# lora_esp32_gps.net
KiCad netlist of a schematic drawn in EAGLE
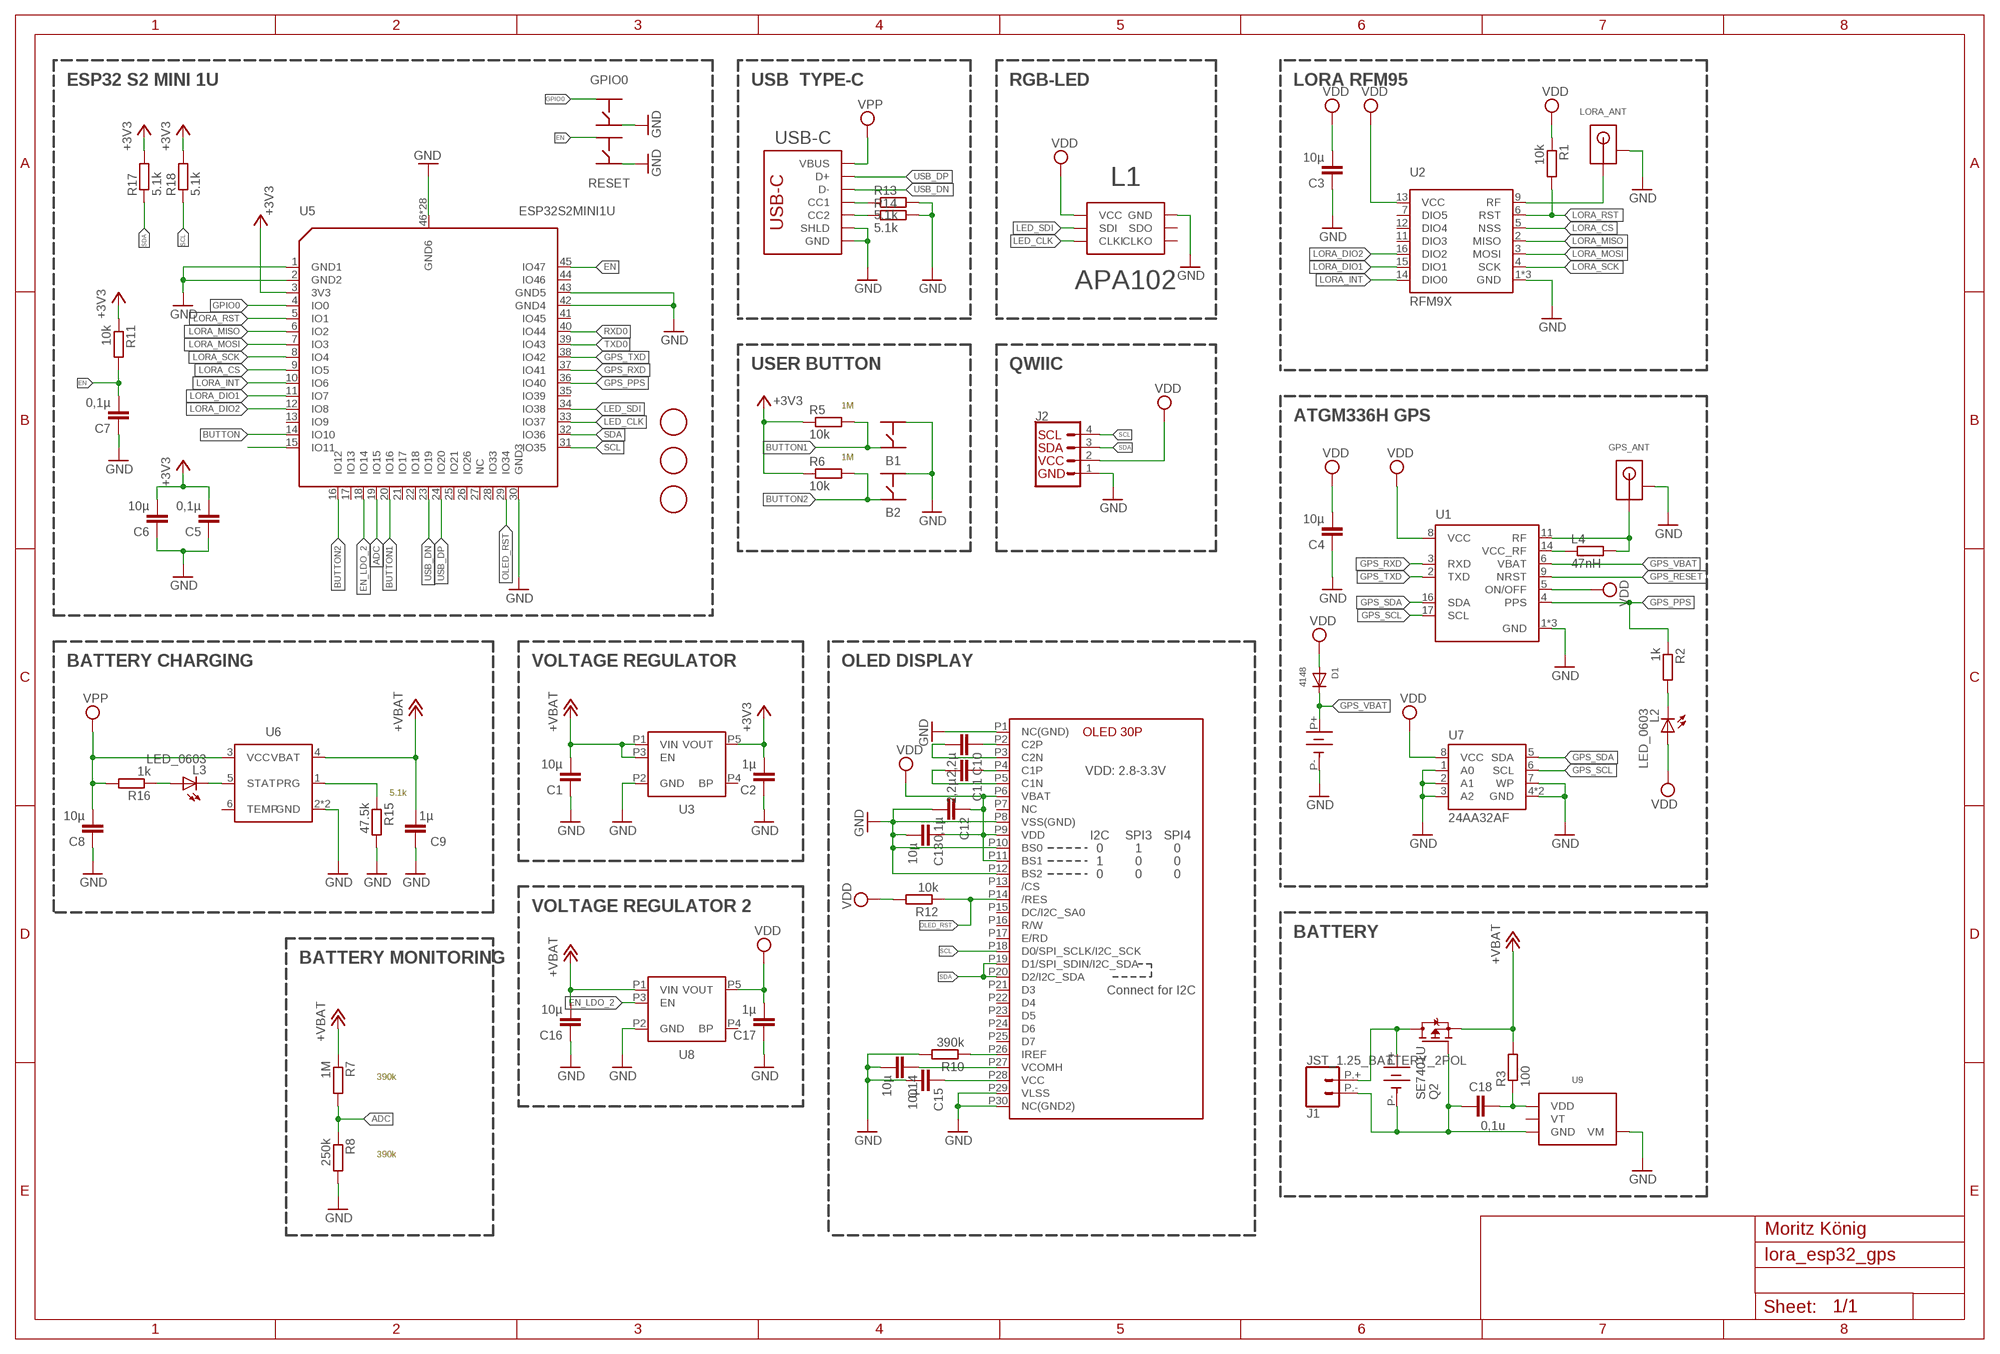
[diagram p0: schematic, sheet 1]

(export (version "E")
  (design (tool "Eeschema 10.0.6"))
  (components
    (comp (ref "B1")
      (value "PTS840ESDGMSMTRLFS")
      (footprint "eagle-import:PTS840ESDGMSMTRLFS")
      (libsource (lib "eagle-import") (part "PTS840ESDGMSMTRLFS"))
    )
    (comp (ref "B2")
      (value "PTS840ESDGMSMTRLFS")
      (footprint "eagle-import:PTS840ESDGMSMTRLFS")
      (libsource (lib "eagle-import") (part "PTS840ESDGMSMTRLFS"))
    )
    (comp (ref "BAT2")
      (value "MS621")
      (footprint "eagle-import:MS621")
      (libsource (lib "eagle-import") (part "MS621"))
    )
    (comp (ref "C1")
      (value "10µ")
      (footprint "eagle-import:C0603")
      (libsource (lib "eagle-import") (part "C-EU_WO_KEEPOUT"))
    )
    (comp (ref "C2")
      (value "1µ")
      (footprint "eagle-import:C0603")
      (libsource (lib "eagle-import") (part "C-EU_WO_KEEPOUT"))
    )
    (comp (ref "C3")
      (value "10µ")
      (footprint "eagle-import:C0603")
      (libsource (lib "eagle-import") (part "C0603"))
    )
    (comp (ref "C4")
      (value "10µ")
      (footprint "eagle-import:C0603")
      (libsource (lib "eagle-import") (part "C0603"))
    )
    (comp (ref "C5")
      (value "0,1µ")
      (footprint "eagle-import:C0603")
      (libsource (lib "eagle-import") (part "C-EU_WO_KEEPOUT"))
    )
    (comp (ref "C6")
      (value "10µ")
      (footprint "eagle-import:C0603")
      (libsource (lib "eagle-import") (part "C-EU_WO_KEEPOUT"))
    )
    (comp (ref "C7")
      (value "0,1µ")
      (footprint "eagle-import:C0603")
      (libsource (lib "eagle-import") (part "C0603"))
    )
    (comp (ref "C8")
      (value "10µ")
      (footprint "eagle-import:C0603")
      (libsource (lib "eagle-import") (part "C0603"))
    )
    (comp (ref "C9")
      (value "1µ")
      (footprint "eagle-import:C0603")
      (libsource (lib "eagle-import") (part "C0603"))
    )
    (comp (ref "C10")
      (value "2,2µ")
      (footprint "eagle-import:C0603")
      (libsource (lib "eagle-import") (part "C-EU_WO_KEEPOUT"))
    )
    (comp (ref "C11")
      (value "2,2µ")
      (footprint "eagle-import:C0603")
      (libsource (lib "eagle-import") (part "C-EU_WO_KEEPOUT"))
    )
    (comp (ref "C12")
      (value "0,1µ")
      (footprint "eagle-import:C0603")
      (libsource (lib "eagle-import") (part "C-EU_WO_KEEPOUT"))
    )
    (comp (ref "C13")
      (value "10µ")
      (footprint "eagle-import:C0603")
      (libsource (lib "eagle-import") (part "C-EU_WO_KEEPOUT"))
    )
    (comp (ref "C14")
      (value "10µ")
      (footprint "eagle-import:C0603")
      (libsource (lib "eagle-import") (part "C-EU_WO_KEEPOUT"))
    )
    (comp (ref "C15")
      (value "10µ")
      (footprint "eagle-import:C0603")
      (libsource (lib "eagle-import") (part "C-EU_WO_KEEPOUT"))
    )
    (comp (ref "C16")
      (value "10µ")
      (footprint "eagle-import:C0603")
      (libsource (lib "eagle-import") (part "C-EU_WO_KEEPOUT"))
    )
    (comp (ref "C17")
      (value "1µ")
      (footprint "eagle-import:C0603")
      (libsource (lib "eagle-import") (part "C-EU_WO_KEEPOUT"))
    )
    (comp (ref "C18")
      (value "0,1u")
      (footprint "eagle-import:C0603")
      (libsource (lib "eagle-import") (part "C0603"))
    )
    (comp (ref "D1")
      (value "4148")
      (footprint "eagle-import:SOD-323F")
      (libsource (lib "eagle-import") (part "DIODESOD-323F"))
    )
    (comp (ref "FID1")
      (value "FIDUCIAL")
      (footprint "eagle-import:FIDUCIAL_1MM")
      (libsource (lib "eagle-import") (part "FIDUCIAL"))
    )
    (comp (ref "FID2")
      (value "FIDUCIAL")
      (footprint "eagle-import:FIDUCIAL_1MM")
      (libsource (lib "eagle-import") (part "FIDUCIAL"))
    )
    (comp (ref "FID3")
      (value "FIDUCIAL")
      (footprint "eagle-import:FIDUCIAL_1MM")
      (libsource (lib "eagle-import") (part "FIDUCIAL"))
    )
    (comp (ref "GPIO0")
      (value "BUTTON_4PIN_TS_1177")
      (footprint "eagle-import:TS-1177-C-B-B")
      (libsource (lib "eagle-import") (part "BUTTON_4PIN_TS_1177"))
    )
    (comp (ref "GPS_ANT")
      (value "UFL_ANT_CONNECTOR")
      (footprint "eagle-import:UFL_ANT_CONNECTOR")
      (libsource (lib "eagle-import") (part "UFL_ANT_CONNECTOR"))
    )
    (comp (ref "J1")
      (value "JST_1.25_BATTERY_2POL")
      (footprint "eagle-import:JST_1.25MM_2POL")
      (libsource (lib "eagle-import") (part "JST_1.25_BATTERY_2POL"))
    )
    (comp (ref "J2")
      (value "QWIIC_CONNECTORJS-1MM")
      (footprint "eagle-import:1X04_1MM_RA")
      (libsource (lib "eagle-import") (part "QWIIC_CONNECTORJS-1MM"))
    )
    (comp (ref "L1")
      (value "APA102_2020")
      (footprint "eagle-import:APA102_2020")
      (libsource (lib "eagle-import") (part "APA102_2020"))
    )
    (comp (ref "L2")
      (value "LED_0603")
      (footprint "eagle-import:CHIPLED_0603")
      (libsource (lib "eagle-import") (part "LED_0603"))
    )
    (comp (ref "L3")
      (value "LED_0603")
      (footprint "eagle-import:CHIPLED_0603")
      (libsource (lib "eagle-import") (part "LED_0603"))
    )
    (comp (ref "L4")
      (value "47nH")
      (footprint "eagle-import:R0402")
      (libsource (lib "eagle-import") (part "R0402"))
    )
    (comp (ref "LORA_ANT")
      (value "UFL_ANT_CONNECTOR")
      (footprint "eagle-import:UFL_ANT_CONNECTOR")
      (libsource (lib "eagle-import") (part "UFL_ANT_CONNECTOR"))
    )
    (comp (ref "Q2")
      (value "SE7401U")
      (footprint "eagle-import:SOT323")
      (libsource (lib "eagle-import") (part "SE7401U"))
    )
    (comp (ref "R1")
      (value "10k")
      (footprint "eagle-import:R0603")
      (libsource (lib "eagle-import") (part "R0603"))
    )
    (comp (ref "R2")
      (value "1k")
      (footprint "eagle-import:R0603")
      (libsource (lib "eagle-import") (part "R0603"))
    )
    (comp (ref "R3")
      (value "100")
      (footprint "eagle-import:R0603")
      (libsource (lib "eagle-import") (part "R0603"))
    )
    (comp (ref "R5")
      (value "10k")
      (footprint "eagle-import:R0603")
      (libsource (lib "eagle-import") (part "R0603"))
    )
    (comp (ref "R6")
      (value "10k")
      (footprint "eagle-import:R0603")
      (libsource (lib "eagle-import") (part "R0603"))
    )
    (comp (ref "R7")
      (value "1M")
      (footprint "eagle-import:R0603")
      (libsource (lib "eagle-import") (part "R0603"))
    )
    (comp (ref "R8")
      (value "250k")
      (footprint "eagle-import:R0603")
      (libsource (lib "eagle-import") (part "R0603"))
    )
    (comp (ref "R10")
      (value "390k")
      (footprint "eagle-import:R0603")
      (libsource (lib "eagle-import") (part "R-EU_WO_KEEPOUT"))
    )
    (comp (ref "R11")
      (value "10k")
      (footprint "eagle-import:R0603")
      (libsource (lib "eagle-import") (part "R0603"))
    )
    (comp (ref "R12")
      (value "10k")
      (footprint "eagle-import:R0603")
      (libsource (lib "eagle-import") (part "R-EU_WO_KEEPOUT"))
    )
    (comp (ref "R13")
      (value "5.1k")
      (footprint "eagle-import:R0603")
      (libsource (lib "eagle-import") (part "R0603"))
    )
    (comp (ref "R14")
      (value "5.1k")
      (footprint "eagle-import:R0603")
      (libsource (lib "eagle-import") (part "R0603"))
    )
    (comp (ref "R15")
      (value "47.5k")
      (footprint "eagle-import:R0603")
      (libsource (lib "eagle-import") (part "R0603"))
    )
    (comp (ref "R16")
      (value "1k")
      (footprint "eagle-import:R0603")
      (libsource (lib "eagle-import") (part "R0603"))
    )
    (comp (ref "R17")
      (value "5.1k")
      (footprint "eagle-import:R0603")
      (libsource (lib "eagle-import") (part "R-EU_WO_KEEPOUT"))
    )
    (comp (ref "R18")
      (value "5.1k")
      (footprint "eagle-import:R0603")
      (libsource (lib "eagle-import") (part "R-EU_WO_KEEPOUT"))
    )
    (comp (ref "RESET")
      (value "BUTTON_4PIN_TS_1177")
      (footprint "eagle-import:TS-1177-C-B-B")
      (libsource (lib "eagle-import") (part "BUTTON_4PIN_TS_1177"))
    )
    (comp (ref "U$2")
      (value "BATTERY_KEYSTONE_1051")
      (footprint "eagle-import:KEYSTONE_1051")
      (libsource (lib "eagle-import") (part "BATTERY_KEYSTONE_1051"))
    )
    (comp (ref "U1")
      (value "ATGM336H")
      (footprint "eagle-import:ATGM336H-MODULE")
      (libsource (lib "eagle-import") (part "ATGM336H"))
    )
    (comp (ref "U2")
      (value "RFM9X")
      (footprint "eagle-import:LORA_RFM9X")
      (libsource (lib "eagle-import") (part "RFM9X"))
    )
    (comp (ref "U3")
      (value "RT9193_SC70-5")
      (footprint "eagle-import:SC-70-5")
      (libsource (lib "eagle-import") (part "RT9193_SC70-5"))
    )
    (comp (ref "U4")
      (value "OLD_096_SSD1306_30P_2B")
      (footprint "eagle-import:OLED_096_30P_B")
      (libsource (lib "eagle-import") (part "OLD_096_SSD1306_30P_2B"))
    )
    (comp (ref "U5")
      (value "ESP32S2MINI1U")
      (footprint "eagle-import:ESP32-S2-MINI-1U")
      (libsource (lib "eagle-import") (part "ESP32-S2-MINI-1U"))
    )
    (comp (ref "U6")
      (value "WS4518D")
      (footprint "eagle-import:DFN-6")
      (libsource (lib "eagle-import") (part "WS4518D"))
    )
    (comp (ref "U7")
      (value "24AA32AF")
      (footprint "eagle-import:TDFN8")
      (libsource (lib "eagle-import") (part "24AA32AF"))
    )
    (comp (ref "U8")
      (value "RT9193_SC70-5")
      (footprint "eagle-import:SC-70-5")
      (libsource (lib "eagle-import") (part "RT9193_SC70-5"))
    )
    (comp (ref "U9")
      (value "XB5353A")
      (footprint "eagle-import:SOT23-5")
      (libsource (lib "eagle-import") (part "XB5353A"))
    )
    (comp (ref "USB-C")
      (value "USB_C_C393939")
      (footprint "eagle-import:USBC_C393939")
      (libsource (lib "eagle-import") (part "USB_C_C393939"))
    )
  )
  (nets
    (net (code "1") (name "+3V3") (class "Default")
      (node (ref "C2") (pin "2") (pinfunction "2_2") (pintype "passive"))
      (node (ref "C5") (pin "2") (pinfunction "2_2") (pintype "passive"))
      (node (ref "C6") (pin "2") (pinfunction "2_2") (pintype "passive"))
      (node (ref "R11") (pin "1") (pinfunction "1_1") (pintype "passive"))
      (node (ref "R17") (pin "2") (pinfunction "2_2") (pintype "passive"))
      (node (ref "R18") (pin "2") (pinfunction "2_2") (pintype "passive"))
      (node (ref "R5") (pin "1") (pinfunction "1_1") (pintype "passive"))
      (node (ref "R6") (pin "1") (pinfunction "1_1") (pintype "passive"))
      (node (ref "U3") (pin "P5") (pinfunction "VOUT_P5") (pintype "bidirectional"))
      (node (ref "U5") (pin "3") (pinfunction "3V3_3") (pintype "bidirectional"))
    )
    (net (code "2") (name "+VBAT") (class "Default")
      (node (ref "C1") (pin "2") (pinfunction "2_2") (pintype "passive"))
      (node (ref "C16") (pin "2") (pinfunction "2_2") (pintype "passive"))
      (node (ref "C9") (pin "2") (pinfunction "2_2") (pintype "passive"))
      (node (ref "Q2") (pin "2") (pinfunction "S_2") (pintype "passive"))
      (node (ref "R3") (pin "2") (pinfunction "2_2") (pintype "passive"))
      (node (ref "R7") (pin "1") (pinfunction "1_1") (pintype "passive"))
      (node (ref "U3") (pin "P1") (pinfunction "VIN_P1") (pintype "bidirectional"))
      (node (ref "U3") (pin "P3") (pinfunction "EN_P3") (pintype "bidirectional"))
      (node (ref "U6") (pin "4") (pinfunction "VBAT_4") (pintype "bidirectional"))
      (node (ref "U8") (pin "P1") (pinfunction "VIN_P1") (pintype "bidirectional"))
    )
    (net (code "3") (name "ADC") (class "Default")
      (node (ref "R7") (pin "2") (pinfunction "2_2") (pintype "passive"))
      (node (ref "R8") (pin "1") (pinfunction "1_1") (pintype "passive"))
      (node (ref "U5") (pin "19") (pinfunction "IO15_19") (pintype "bidirectional"))
    )
    (net (code "4") (name "BUTTON") (class "Default")
      (node (ref "U5") (pin "14") (pinfunction "IO10_14") (pintype "bidirectional"))
    )
    (net (code "5") (name "BUTTON1") (class "Default")
      (node (ref "B1") (pin "2") (pinfunction "2_2") (pintype "bidirectional"))
      (node (ref "R5") (pin "2") (pinfunction "2_2") (pintype "passive"))
      (node (ref "U5") (pin "20") (pinfunction "IO16_20") (pintype "bidirectional"))
    )
    (net (code "6") (name "BUTTON2") (class "Default")
      (node (ref "B2") (pin "2") (pinfunction "2_2") (pintype "bidirectional"))
      (node (ref "R6") (pin "2") (pinfunction "2_2") (pintype "passive"))
      (node (ref "U5") (pin "16") (pinfunction "IO12_16") (pintype "bidirectional"))
    )
    (net (code "7") (name "EN") (class "Default")
      (node (ref "C7") (pin "2") (pinfunction "2_2") (pintype "passive"))
      (node (ref "R11") (pin "2") (pinfunction "2_2") (pintype "passive"))
      (node (ref "RESET") (pin "P4") (pinfunction "4_P4") (pintype "bidirectional"))
      (node (ref "U5") (pin "45") (pinfunction "IO47_45") (pintype "bidirectional"))
    )
    (net (code "8") (name "EN_LDO_2") (class "Default")
      (node (ref "U5") (pin "18") (pinfunction "IO14_18") (pintype "bidirectional"))
      (node (ref "U8") (pin "P3") (pinfunction "EN_P3") (pintype "bidirectional"))
    )
    (net (code "9") (name "GND") (class "Default")
      (node (ref "B1") (pin "3") (pinfunction "3_3") (pintype "bidirectional"))
      (node (ref "B2") (pin "3") (pinfunction "3_3") (pintype "bidirectional"))
      (node (ref "BAT2") (pin "P-") (pinfunction "GND_P-") (pintype "bidirectional"))
      (node (ref "C1") (pin "1") (pinfunction "1_1") (pintype "passive"))
      (node (ref "C12") (pin "2") (pinfunction "2_2") (pintype "passive"))
      (node (ref "C13") (pin "2") (pinfunction "2_2") (pintype "passive"))
      (node (ref "C14") (pin "2") (pinfunction "2_2") (pintype "passive"))
      (node (ref "C15") (pin "2") (pinfunction "2_2") (pintype "passive"))
      (node (ref "C16") (pin "1") (pinfunction "1_1") (pintype "passive"))
      (node (ref "C17") (pin "1") (pinfunction "1_1") (pintype "passive"))
      (node (ref "C2") (pin "1") (pinfunction "1_1") (pintype "passive"))
      (node (ref "C3") (pin "1") (pinfunction "1_1") (pintype "passive"))
      (node (ref "C4") (pin "1") (pinfunction "1_1") (pintype "passive"))
      (node (ref "C5") (pin "1") (pinfunction "1_1") (pintype "passive"))
      (node (ref "C6") (pin "1") (pinfunction "1_1") (pintype "passive"))
      (node (ref "C7") (pin "1") (pinfunction "1_1") (pintype "passive"))
      (node (ref "C8") (pin "1") (pinfunction "1_1") (pintype "passive"))
      (node (ref "C9") (pin "1") (pinfunction "1_1") (pintype "passive"))
      (node (ref "GPIO0") (pin "P1") (pinfunction "1_P1") (pintype "bidirectional"))
      (node (ref "GPS_ANT") (pin "P1.-") (pinfunction "GND_P1.-") (pintype "bidirectional"))
      (node (ref "GPS_ANT") (pin "P2.-") (pinfunction "GND_P2.-") (pintype "bidirectional"))
      (node (ref "J2") (pin "1") (pinfunction "GND_1") (pintype "power_in"))
      (node (ref "L1") (pin "P6") (pinfunction "GND_P6") (pintype "bidirectional"))
      (node (ref "L1") (pin "P6.1") (pinfunction "GND_P6.1") (pintype "bidirectional"))
      (node (ref "LORA_ANT") (pin "P1.-") (pinfunction "GND_P1.-") (pintype "bidirectional"))
      (node (ref "LORA_ANT") (pin "P2.-") (pinfunction "GND_P2.-") (pintype "bidirectional"))
      (node (ref "R10") (pin "2") (pinfunction "2_2") (pintype "passive"))
      (node (ref "R13") (pin "2") (pinfunction "2_2") (pintype "passive"))
      (node (ref "R14") (pin "2") (pinfunction "2_2") (pintype "passive"))
      (node (ref "R15") (pin "2") (pinfunction "2_2") (pintype "passive"))
      (node (ref "R8") (pin "2") (pinfunction "2_2") (pintype "passive"))
      (node (ref "RESET") (pin "P1") (pinfunction "1_P1") (pintype "bidirectional"))
      (node (ref "U1") (pin "1") (pinfunction "GND_1") (pintype "bidirectional"))
      (node (ref "U1") (pin "10") (pinfunction "GND_10") (pintype "bidirectional"))
      (node (ref "U1") (pin "12") (pinfunction "GND_12") (pintype "bidirectional"))
      (node (ref "U2") (pin "1") (pinfunction "GND_1") (pintype "bidirectional"))
      (node (ref "U2") (pin "10") (pinfunction "GND_10") (pintype "bidirectional"))
      (node (ref "U2") (pin "8") (pinfunction "GND_8") (pintype "bidirectional"))
      (node (ref "U3") (pin "P2") (pinfunction "GND_P2") (pintype "bidirectional"))
      (node (ref "U4") (pin "P1") (pinfunction "NC(GND)_P1") (pintype "bidirectional"))
      (node (ref "U4") (pin "P10") (pinfunction "BS0_P10") (pintype "bidirectional"))
      (node (ref "U4") (pin "P12") (pinfunction "BS2_P12") (pintype "bidirectional"))
      (node (ref "U4") (pin "P29") (pinfunction "VLSS_P29") (pintype "bidirectional"))
      (node (ref "U4") (pin "P30") (pinfunction "NC(GND2)_P30") (pintype "bidirectional"))
      (node (ref "U4") (pin "P8") (pinfunction "VSS(GND)_P8") (pintype "bidirectional"))
      (node (ref "U5") (pin "1") (pinfunction "GND1_1") (pintype "bidirectional"))
      (node (ref "U5") (pin "2") (pinfunction "GND2_2") (pintype "bidirectional"))
      (node (ref "U5") (pin "30") (pinfunction "GND3_30") (pintype "bidirectional"))
      (node (ref "U5") (pin "42") (pinfunction "GND4_42") (pintype "bidirectional"))
      (node (ref "U5") (pin "43") (pinfunction "GND5_43") (pintype "bidirectional"))
      (node (ref "U5") (pin "46") (pinfunction "GND6_46") (pintype "bidirectional"))
      (node (ref "U5") (pin "47") (pinfunction "GND6_47") (pintype "bidirectional"))
      (node (ref "U5") (pin "48") (pinfunction "GND6_48") (pintype "bidirectional"))
      (node (ref "U5") (pin "49") (pinfunction "GND6_49") (pintype "bidirectional"))
      (node (ref "U5") (pin "50") (pinfunction "GND6_50") (pintype "bidirectional"))
      (node (ref "U5") (pin "51") (pinfunction "GND6_51") (pintype "bidirectional"))
      (node (ref "U5") (pin "52") (pinfunction "GND6_52") (pintype "bidirectional"))
      (node (ref "U5") (pin "53") (pinfunction "GND6_53") (pintype "bidirectional"))
      (node (ref "U5") (pin "54") (pinfunction "GND6_54") (pintype "bidirectional"))
      (node (ref "U5") (pin "55") (pinfunction "GND6_55") (pintype "bidirectional"))
      (node (ref "U5") (pin "56") (pinfunction "GND6_56") (pintype "bidirectional"))
      (node (ref "U5") (pin "57") (pinfunction "GND6_57") (pintype "bidirectional"))
      (node (ref "U5") (pin "58") (pinfunction "GND6_58") (pintype "bidirectional"))
      (node (ref "U5") (pin "59") (pinfunction "GND6_59") (pintype "bidirectional"))
      (node (ref "U5") (pin "60") (pinfunction "GND6_60") (pintype "bidirectional"))
      (node (ref "U5") (pin "61") (pinfunction "GND6_61") (pintype "bidirectional"))
      (node (ref "U5") (pin "62") (pinfunction "GND6_62") (pintype "bidirectional"))
      (node (ref "U5") (pin "63") (pinfunction "GND6_63") (pintype "bidirectional"))
      (node (ref "U5") (pin "64") (pinfunction "GND6_64") (pintype "bidirectional"))
      (node (ref "U5") (pin "65") (pinfunction "GND6_65") (pintype "bidirectional"))
      (node (ref "U5") (pin "66") (pinfunction "GND6_66") (pintype "bidirectional"))
      (node (ref "U5") (pin "67") (pinfunction "GND6_67") (pintype "bidirectional"))
      (node (ref "U5") (pin "68") (pinfunction "GND6_68") (pintype "bidirectional"))
      (node (ref "U5") (pin "69") (pinfunction "GND6_69") (pintype "bidirectional"))
      (node (ref "U5") (pin "70") (pinfunction "GND6_70") (pintype "bidirectional"))
      (node (ref "U5") (pin "71") (pinfunction "GND6_71") (pintype "bidirectional"))
      (node (ref "U5") (pin "72") (pinfunction "GND6_72") (pintype "bidirectional"))
      (node (ref "U5") (pin "73") (pinfunction "GND6_73") (pintype "bidirectional"))
      (node (ref "U6") (pin "2") (pinfunction "GND_2") (pintype "bidirectional"))
      (node (ref "U6") (pin "EXP") (pinfunction "GND_EXP") (pintype "bidirectional"))
      (node (ref "U7") (pin "1") (pinfunction "A0_1") (pintype "bidirectional"))
      (node (ref "U7") (pin "2") (pinfunction "A1_2") (pintype "bidirectional"))
      (node (ref "U7") (pin "3") (pinfunction "A2_3") (pintype "bidirectional"))
      (node (ref "U7") (pin "4") (pinfunction "GND_4") (pintype "bidirectional"))
      (node (ref "U7") (pin "7") (pinfunction "WP_7") (pintype "bidirectional"))
      (node (ref "U7") (pin "EXP") (pinfunction "GND_EXP") (pintype "bidirectional"))
      (node (ref "U8") (pin "P2") (pinfunction "GND_P2") (pintype "bidirectional"))
      (node (ref "U9") (pin "4") (pinfunction "VM_4") (pintype "bidirectional"))
      (node (ref "U9") (pin "5") (pinfunction "VM_5") (pintype "bidirectional"))
      (node (ref "USB-C") (pin "A1B12") (pinfunction "GND_A1B12") (pintype "bidirectional"))
      (node (ref "USB-C") (pin "B1A12") (pinfunction "GND_B1A12") (pintype "bidirectional"))
      (node (ref "USB-C") (pin "S1") (pinfunction "SHLD_S1") (pintype "bidirectional"))
      (node (ref "USB-C") (pin "S2") (pinfunction "SHLD_S2") (pintype "bidirectional"))
      (node (ref "USB-C") (pin "S3") (pinfunction "SHLD_S3") (pintype "bidirectional"))
      (node (ref "USB-C") (pin "S4") (pinfunction "SHLD_S4") (pintype "bidirectional"))
    )
    (net (code "10") (name "GPIO0") (class "Default")
      (node (ref "GPIO0") (pin "P4") (pinfunction "4_P4") (pintype "bidirectional"))
      (node (ref "U5") (pin "4") (pinfunction "IO0_4") (pintype "bidirectional"))
    )
    (net (code "11") (name "GPS_PPS") (class "Default")
      (node (ref "R2") (pin "1") (pinfunction "1_1") (pintype "passive"))
      (node (ref "U1") (pin "4") (pinfunction "PPS_4") (pintype "bidirectional"))
      (node (ref "U5") (pin "36") (pinfunction "IO40_36") (pintype "bidirectional"))
    )
    (net (code "12") (name "GPS_RESET") (class "Default")
      (node (ref "U1") (pin "9") (pinfunction "NRST_9") (pintype "bidirectional"))
    )
    (net (code "13") (name "GPS_RXD") (class "Default")
      (node (ref "U1") (pin "3") (pinfunction "RXD_3") (pintype "bidirectional"))
      (node (ref "U5") (pin "37") (pinfunction "IO41_37") (pintype "bidirectional"))
    )
    (net (code "14") (name "GPS_SCL") (class "Default")
      (node (ref "U1") (pin "17") (pinfunction "SCL_17") (pintype "bidirectional"))
      (node (ref "U7") (pin "6") (pinfunction "SCL_6") (pintype "bidirectional"))
    )
    (net (code "15") (name "GPS_SDA") (class "Default")
      (node (ref "U1") (pin "16") (pinfunction "SDA_16") (pintype "bidirectional"))
      (node (ref "U7") (pin "5") (pinfunction "SDA_5") (pintype "bidirectional"))
    )
    (net (code "16") (name "GPS_TXD") (class "Default")
      (node (ref "U1") (pin "2") (pinfunction "TXD_2") (pintype "bidirectional"))
      (node (ref "U5") (pin "38") (pinfunction "IO42_38") (pintype "bidirectional"))
    )
    (net (code "17") (name "GPS_VBAT") (class "Default")
      (node (ref "BAT2") (pin "P+") (pinfunction "VCC_P+") (pintype "bidirectional"))
      (node (ref "D1") (pin "C") (pinfunction "C_C") (pintype "passive"))
      (node (ref "U1") (pin "6") (pinfunction "VBAT_6") (pintype "bidirectional"))
    )
    (net (code "18") (name "LED_CLK") (class "Default")
      (node (ref "L1") (pin "P5") (pinfunction "CLKI_P5") (pintype "bidirectional"))
      (node (ref "U5") (pin "33") (pinfunction "IO37_33") (pintype "bidirectional"))
    )
    (net (code "19") (name "LED_SDI") (class "Default")
      (node (ref "L1") (pin "P4") (pinfunction "SDI_P4") (pintype "bidirectional"))
      (node (ref "U5") (pin "34") (pinfunction "IO38_34") (pintype "bidirectional"))
    )
    (net (code "20") (name "LORA_CS") (class "Default")
      (node (ref "U2") (pin "5") (pinfunction "NSS_5") (pintype "bidirectional"))
      (node (ref "U5") (pin "9") (pinfunction "IO5_9") (pintype "bidirectional"))
    )
    (net (code "21") (name "LORA_DIO1") (class "Default")
      (node (ref "U2") (pin "15") (pinfunction "DIO1_15") (pintype "bidirectional"))
      (node (ref "U5") (pin "11") (pinfunction "IO7_11") (pintype "bidirectional"))
    )
    (net (code "22") (name "LORA_DIO2") (class "Default")
      (node (ref "U2") (pin "16") (pinfunction "DIO2_16") (pintype "bidirectional"))
      (node (ref "U5") (pin "12") (pinfunction "IO8_12") (pintype "bidirectional"))
    )
    (net (code "23") (name "LORA_INT") (class "Default")
      (node (ref "U2") (pin "14") (pinfunction "DIO0_14") (pintype "bidirectional"))
      (node (ref "U5") (pin "10") (pinfunction "IO6_10") (pintype "bidirectional"))
    )
    (net (code "24") (name "LORA_MISO") (class "Default")
      (node (ref "U2") (pin "2") (pinfunction "MISO_2") (pintype "bidirectional"))
      (node (ref "U5") (pin "6") (pinfunction "IO2_6") (pintype "bidirectional"))
    )
    (net (code "25") (name "LORA_MOSI") (class "Default")
      (node (ref "U2") (pin "3") (pinfunction "MOSI_3") (pintype "bidirectional"))
      (node (ref "U5") (pin "7") (pinfunction "IO3_7") (pintype "bidirectional"))
    )
    (net (code "26") (name "LORA_RST") (class "Default")
      (node (ref "R1") (pin "2") (pinfunction "2_2") (pintype "passive"))
      (node (ref "U2") (pin "6") (pinfunction "RST_6") (pintype "bidirectional"))
      (node (ref "U5") (pin "5") (pinfunction "IO1_5") (pintype "bidirectional"))
    )
    (net (code "27") (name "LORA_SCK") (class "Default")
      (node (ref "U2") (pin "4") (pinfunction "SCK_4") (pintype "bidirectional"))
      (node (ref "U5") (pin "8") (pinfunction "IO4_8") (pintype "bidirectional"))
    )
    (net (code "28") (name "Net-(J1-1)") (class "Default")
      (node (ref "J1") (pin "P.+") (pinfunction "1_P.+") (pintype "passive"))
      (node (ref "Q2") (pin "3") (pinfunction "D_3") (pintype "passive"))
      (node (ref "U$2") (pin "P+") (pinfunction "VCC_P+") (pintype "bidirectional"))
    )
    (net (code "29") (name "Net-(J1-2)") (class "Default")
      (node (ref "C18") (pin "1") (pinfunction "1_1") (pintype "passive"))
      (node (ref "J1") (pin "P.-") (pinfunction "2_P.-") (pintype "passive"))
      (node (ref "Q2") (pin "1") (pinfunction "G_1") (pintype "passive"))
      (node (ref "U$2") (pin "P-") (pinfunction "GND_P-") (pintype "bidirectional"))
      (node (ref "U9") (pin "2") (pinfunction "GND_2") (pintype "bidirectional"))
    )
    (net (code "30") (name "Net-(L2-C)") (class "Default")
      (node (ref "L2") (pin "P$1") (pinfunction "C_P$1") (pintype "passive"))
      (node (ref "R2") (pin "2") (pinfunction "2_2") (pintype "passive"))
    )
    (net (code "31") (name "Net-(L3-A)") (class "Default")
      (node (ref "L3") (pin "P$2") (pinfunction "A_P$2") (pintype "passive"))
      (node (ref "R16") (pin "1") (pinfunction "1_1") (pintype "passive"))
    )
    (net (code "32") (name "Net-(L3-C)") (class "Default")
      (node (ref "L3") (pin "P$1") (pinfunction "C_P$1") (pintype "passive"))
      (node (ref "U6") (pin "5") (pinfunction "STAT_5") (pintype "bidirectional"))
    )
    (net (code "33") (name "Net-(U1-RF)") (class "Default")
      (node (ref "GPS_ANT") (pin "ANT") (pinfunction "ANT_ANT") (pintype "bidirectional"))
      (node (ref "L4") (pin "2") (pinfunction "2_2") (pintype "passive"))
      (node (ref "U1") (pin "11") (pinfunction "RF_11") (pintype "bidirectional"))
    )
    (net (code "34") (name "Net-(U1-VCC_RF)") (class "Default")
      (node (ref "L4") (pin "1") (pinfunction "1_1") (pintype "passive"))
      (node (ref "U1") (pin "14") (pinfunction "VCC_RF_14") (pintype "bidirectional"))
    )
    (net (code "35") (name "Net-(U2-RF)") (class "Default")
      (node (ref "LORA_ANT") (pin "ANT") (pinfunction "ANT_ANT") (pintype "bidirectional"))
      (node (ref "U2") (pin "9") (pinfunction "RF_9") (pintype "bidirectional"))
    )
    (net (code "36") (name "Net-(U4-C1N)") (class "Default")
      (node (ref "C11") (pin "2") (pinfunction "2_2") (pintype "passive"))
      (node (ref "U4") (pin "P5") (pinfunction "C1N_P5") (pintype "bidirectional"))
    )
    (net (code "37") (name "Net-(U4-C1P)") (class "Default")
      (node (ref "C11") (pin "1") (pinfunction "1_1") (pintype "passive"))
      (node (ref "U4") (pin "P4") (pinfunction "C1P_P4") (pintype "bidirectional"))
    )
    (net (code "38") (name "Net-(U4-C2N)") (class "Default")
      (node (ref "C10") (pin "2") (pinfunction "2_2") (pintype "passive"))
      (node (ref "U4") (pin "P3") (pinfunction "C2N_P3") (pintype "bidirectional"))
    )
    (net (code "39") (name "Net-(U4-C2P)") (class "Default")
      (node (ref "C10") (pin "1") (pinfunction "1_1") (pintype "passive"))
      (node (ref "U4") (pin "P2") (pinfunction "C2P_P2") (pintype "bidirectional"))
    )
    (net (code "40") (name "Net-(U4-IREF)") (class "Default")
      (node (ref "R10") (pin "1") (pinfunction "1_1") (pintype "passive"))
      (node (ref "U4") (pin "P26") (pinfunction "IREF_P26") (pintype "bidirectional"))
    )
    (net (code "41") (name "Net-(U4-VCC)") (class "Default")
      (node (ref "C15") (pin "1") (pinfunction "1_1") (pintype "passive"))
      (node (ref "U4") (pin "P28") (pinfunction "VCC_P28") (pintype "bidirectional"))
    )
    (net (code "42") (name "Net-(U4-VCOMH)") (class "Default")
      (node (ref "C14") (pin "1") (pinfunction "1_1") (pintype "passive"))
      (node (ref "U4") (pin "P27") (pinfunction "VCOMH_P27") (pintype "bidirectional"))
    )
    (net (code "43") (name "Net-(U6-PRG)") (class "Default")
      (node (ref "R15") (pin "1") (pinfunction "1_1") (pintype "passive"))
      (node (ref "U6") (pin "1") (pinfunction "PRG_1") (pintype "bidirectional"))
    )
    (net (code "44") (name "Net-(U9-VDD)") (class "Default")
      (node (ref "C18") (pin "2") (pinfunction "2_2") (pintype "passive"))
      (node (ref "R3") (pin "1") (pinfunction "1_1") (pintype "passive"))
      (node (ref "U9") (pin "3") (pinfunction "VDD_3") (pintype "bidirectional"))
    )
    (net (code "45") (name "Net-(USB-C-CC1)") (class "Default")
      (node (ref "R13") (pin "1") (pinfunction "1_1") (pintype "passive"))
      (node (ref "USB-C") (pin "A5") (pinfunction "CC1_A5") (pintype "bidirectional"))
    )
    (net (code "46") (name "Net-(USB-C-CC2)") (class "Default")
      (node (ref "R14") (pin "1") (pinfunction "1_1") (pintype "passive"))
      (node (ref "USB-C") (pin "B5") (pinfunction "CC2_B5") (pintype "bidirectional"))
    )
    (net (code "47") (name "OLED_RST") (class "Default")
      (node (ref "R12") (pin "1") (pinfunction "1_1") (pintype "passive"))
      (node (ref "U4") (pin "P14") (pinfunction "/RES_P14") (pintype "bidirectional"))
      (node (ref "U5") (pin "29") (pinfunction "IO34_29") (pintype "bidirectional"))
    )
    (net (code "48") (name "RXD0") (class "Default")
      (node (ref "U5") (pin "40") (pinfunction "IO44_40") (pintype "bidirectional"))
    )
    (net (code "49") (name "SCL") (class "Default")
      (node (ref "J2") (pin "4") (pinfunction "SCL_4") (pintype "passive"))
      (node (ref "R18") (pin "1") (pinfunction "1_1") (pintype "passive"))
      (node (ref "U4") (pin "P18") (pinfunction "D0/SPI_SCLK/I2C_SCK_P18") (pintype "bidirectional"))
      (node (ref "U5") (pin "31") (pinfunction "IO35_31") (pintype "bidirectional"))
    )
    (net (code "50") (name "SDA") (class "Default")
      (node (ref "J2") (pin "3") (pinfunction "SDA_3") (pintype "passive"))
      (node (ref "R17") (pin "1") (pinfunction "1_1") (pintype "passive"))
      (node (ref "U4") (pin "P19") (pinfunction "D1/SPI_SDIN/I2C_SDA_P19") (pintype "bidirectional"))
      (node (ref "U4") (pin "P20") (pinfunction "D2/I2C_SDA_P20") (pintype "bidirectional"))
      (node (ref "U5") (pin "32") (pinfunction "IO36_32") (pintype "bidirectional"))
    )
    (net (code "51") (name "TXD0") (class "Default")
      (node (ref "U5") (pin "39") (pinfunction "IO43_39") (pintype "bidirectional"))
    )
    (net (code "52") (name "USB_DN") (class "Default")
      (node (ref "U5") (pin "23") (pinfunction "IO19_23") (pintype "bidirectional"))
      (node (ref "USB-C") (pin "A7") (pinfunction "D-_A7") (pintype "bidirectional"))
      (node (ref "USB-C") (pin "B7") (pinfunction "D-_B7") (pintype "bidirectional"))
    )
    (net (code "53") (name "USB_DP") (class "Default")
      (node (ref "U5") (pin "24") (pinfunction "IO20_24") (pintype "bidirectional"))
      (node (ref "USB-C") (pin "A6") (pinfunction "D+_A6") (pintype "bidirectional"))
      (node (ref "USB-C") (pin "B6") (pinfunction "D+_B6") (pintype "bidirectional"))
    )
    (net (code "54") (name "VDD") (class "Default")
      (node (ref "C12") (pin "1") (pinfunction "1_1") (pintype "passive"))
      (node (ref "C13") (pin "1") (pinfunction "1_1") (pintype "passive"))
      (node (ref "C17") (pin "2") (pinfunction "2_2") (pintype "passive"))
      (node (ref "C3") (pin "2") (pinfunction "2_2") (pintype "passive"))
      (node (ref "C4") (pin "2") (pinfunction "2_2") (pintype "passive"))
      (node (ref "D1") (pin "A") (pinfunction "A_A") (pintype "passive"))
      (node (ref "J2") (pin "2") (pinfunction "VCC_2") (pintype "power_in"))
      (node (ref "L1") (pin "P1") (pinfunction "VCC_P1") (pintype "bidirectional"))
      (node (ref "L1") (pin "P1.1") (pinfunction "VCC_P1.1") (pintype "bidirectional"))
      (node (ref "L2") (pin "P$2") (pinfunction "A_P$2") (pintype "passive"))
      (node (ref "R1") (pin "1") (pinfunction "1_1") (pintype "passive"))
      (node (ref "R12") (pin "2") (pinfunction "2_2") (pintype "passive"))
      (node (ref "U1") (pin "5") (pinfunction "ON/OFF_5") (pintype "bidirectional"))
      (node (ref "U1") (pin "8") (pinfunction "VCC_8") (pintype "bidirectional"))
      (node (ref "U2") (pin "13") (pinfunction "VCC_13") (pintype "bidirectional"))
      (node (ref "U4") (pin "P11") (pinfunction "BS1_P11") (pintype "bidirectional"))
      (node (ref "U4") (pin "P6") (pinfunction "VBAT_P6") (pintype "bidirectional"))
      (node (ref "U4") (pin "P9") (pinfunction "VDD_P9") (pintype "bidirectional"))
      (node (ref "U7") (pin "8") (pinfunction "VCC_8") (pintype "bidirectional"))
      (node (ref "U8") (pin "P5") (pinfunction "VOUT_P5") (pintype "bidirectional"))
    )
    (net (code "55") (name "VPP") (class "Default")
      (node (ref "C8") (pin "2") (pinfunction "2_2") (pintype "passive"))
      (node (ref "R16") (pin "2") (pinfunction "2_2") (pintype "passive"))
      (node (ref "U6") (pin "3") (pinfunction "VCC_3") (pintype "bidirectional"))
      (node (ref "USB-C") (pin "A4B9") (pinfunction "VBUS_A4B9") (pintype "bidirectional"))
      (node (ref "USB-C") (pin "B4A9") (pinfunction "VBUS_B4A9") (pintype "bidirectional"))
    )
    (net (code "56") (name "unconnected-(B1-Pad1)") (class "Default")
      (node (ref "B1") (pin "1") (pinfunction "1_1") (pintype "bidirectional"))
    )
    (net (code "57") (name "unconnected-(B1-Pad4)") (class "Default")
      (node (ref "B1") (pin "4") (pinfunction "4_4") (pintype "bidirectional"))
    )
    (net (code "58") (name "unconnected-(B1-Pad5)") (class "Default")
      (node (ref "B1") (pin "5") (pinfunction "5_5") (pintype "bidirectional"))
    )
    (net (code "59") (name "unconnected-(B2-Pad1)") (class "Default")
      (node (ref "B2") (pin "1") (pinfunction "1_1") (pintype "bidirectional"))
    )
    (net (code "60") (name "unconnected-(B2-Pad4)") (class "Default")
      (node (ref "B2") (pin "4") (pinfunction "4_4") (pintype "bidirectional"))
    )
    (net (code "61") (name "unconnected-(B2-Pad5)") (class "Default")
      (node (ref "B2") (pin "5") (pinfunction "5_5") (pintype "bidirectional"))
    )
    (net (code "62") (name "unconnected-(GPIO0-2-PadP2)") (class "Default")
      (node (ref "GPIO0") (pin "P2") (pinfunction "2_P2") (pintype "bidirectional"))
    )
    (net (code "63") (name "unconnected-(GPIO0-3-PadP3)") (class "Default")
      (node (ref "GPIO0") (pin "P3") (pinfunction "3_P3") (pintype "bidirectional"))
    )
    (net (code "64") (name "unconnected-(L1-CLKO-PadP2)") (class "Default")
      (node (ref "L1") (pin "P2") (pinfunction "CLKO_P2") (pintype "bidirectional"))
    )
    (net (code "65") (name "unconnected-(L1-SDO-PadP3)") (class "Default")
      (node (ref "L1") (pin "P3") (pinfunction "SDO_P3") (pintype "bidirectional"))
    )
    (net (code "66") (name "unconnected-(RESET-2-PadP2)") (class "Default")
      (node (ref "RESET") (pin "P2") (pinfunction "2_P2") (pintype "bidirectional"))
    )
    (net (code "67") (name "unconnected-(RESET-3-PadP3)") (class "Default")
      (node (ref "RESET") (pin "P3") (pinfunction "3_P3") (pintype "bidirectional"))
    )
    (net (code "68") (name "unconnected-(U2-DIO3-Pad11)") (class "Default")
      (node (ref "U2") (pin "11") (pinfunction "DIO3_11") (pintype "bidirectional"))
    )
    (net (code "69") (name "unconnected-(U2-DIO4-Pad12)") (class "Default")
      (node (ref "U2") (pin "12") (pinfunction "DIO4_12") (pintype "bidirectional"))
    )
    (net (code "70") (name "unconnected-(U2-DIO5-Pad7)") (class "Default")
      (node (ref "U2") (pin "7") (pinfunction "DIO5_7") (pintype "bidirectional"))
    )
    (net (code "71") (name "unconnected-(U3-BP-PadP4)") (class "Default")
      (node (ref "U3") (pin "P4") (pinfunction "BP_P4") (pintype "bidirectional"))
    )
    (net (code "72") (name "unconnected-(U4-D3-PadP21)") (class "Default")
      (node (ref "U4") (pin "P21") (pinfunction "D3_P21") (pintype "bidirectional"))
    )
    (net (code "73") (name "unconnected-(U4-D4-PadP22)") (class "Default")
      (node (ref "U4") (pin "P22") (pinfunction "D4_P22") (pintype "bidirectional"))
    )
    (net (code "74") (name "unconnected-(U4-D5-PadP23)") (class "Default")
      (node (ref "U4") (pin "P23") (pinfunction "D5_P23") (pintype "bidirectional"))
    )
    (net (code "75") (name "unconnected-(U4-D6-PadP24)") (class "Default")
      (node (ref "U4") (pin "P24") (pinfunction "D6_P24") (pintype "bidirectional"))
    )
    (net (code "76") (name "unconnected-(U4-D7-PadP25)") (class "Default")
      (node (ref "U4") (pin "P25") (pinfunction "D7_P25") (pintype "bidirectional"))
    )
    (net (code "77") (name "unconnected-(U4-DC{slash}I2C_SA0-PadP15)") (class "Default")
      (node (ref "U4") (pin "P15") (pinfunction "DC/I2C_SA0_P15") (pintype "bidirectional"))
    )
    (net (code "78") (name "unconnected-(U4-E{slash}RD-PadP17)") (class "Default")
      (node (ref "U4") (pin "P17") (pinfunction "E/RD_P17") (pintype "bidirectional"))
    )
    (net (code "79") (name "unconnected-(U4-NC-PadP7)") (class "Default")
      (node (ref "U4") (pin "P7") (pinfunction "NC_P7") (pintype "bidirectional"))
    )
    (net (code "80") (name "unconnected-(U4-R{slash}W-PadP16)") (class "Default")
      (node (ref "U4") (pin "P16") (pinfunction "R/W_P16") (pintype "bidirectional"))
    )
    (net (code "81") (name "unconnected-(U4-{slash}CS-PadP13)") (class "Default")
      (node (ref "U4") (pin "P13") (pinfunction "/CS_P13") (pintype "bidirectional"))
    )
    (net (code "82") (name "unconnected-(U5-IO9-Pad13)") (class "Default")
      (node (ref "U5") (pin "13") (pinfunction "IO9_13") (pintype "bidirectional"))
    )
    (net (code "83") (name "unconnected-(U5-IO11-Pad15)") (class "Default")
      (node (ref "U5") (pin "15") (pinfunction "IO11_15") (pintype "bidirectional"))
    )
    (net (code "84") (name "unconnected-(U5-IO13-Pad17)") (class "Default")
      (node (ref "U5") (pin "17") (pinfunction "IO13_17") (pintype "bidirectional"))
    )
    (net (code "85") (name "unconnected-(U5-IO17-Pad21)") (class "Default")
      (node (ref "U5") (pin "21") (pinfunction "IO17_21") (pintype "bidirectional"))
    )
    (net (code "86") (name "unconnected-(U5-IO18-Pad22)") (class "Default")
      (node (ref "U5") (pin "22") (pinfunction "IO18_22") (pintype "bidirectional"))
    )
    (net (code "87") (name "unconnected-(U5-IO21-Pad25)") (class "Default")
      (node (ref "U5") (pin "25") (pinfunction "IO21_25") (pintype "bidirectional"))
    )
    (net (code "88") (name "unconnected-(U5-IO26-Pad26)") (class "Default")
      (node (ref "U5") (pin "26") (pinfunction "IO26_26") (pintype "bidirectional"))
    )
    (net (code "89") (name "unconnected-(U5-IO33-Pad28)") (class "Default")
      (node (ref "U5") (pin "28") (pinfunction "IO33_28") (pintype "bidirectional"))
    )
    (net (code "90") (name "unconnected-(U5-IO39-Pad35)") (class "Default")
      (node (ref "U5") (pin "35") (pinfunction "IO39_35") (pintype "bidirectional"))
    )
    (net (code "91") (name "unconnected-(U5-IO45-Pad41)") (class "Default")
      (node (ref "U5") (pin "41") (pinfunction "IO45_41") (pintype "bidirectional"))
    )
    (net (code "92") (name "unconnected-(U5-IO46-Pad44)") (class "Default")
      (node (ref "U5") (pin "44") (pinfunction "IO46_44") (pintype "bidirectional"))
    )
    (net (code "93") (name "unconnected-(U5-NC-Pad27)") (class "Default")
      (node (ref "U5") (pin "27") (pinfunction "NC_27") (pintype "bidirectional"))
    )
    (net (code "94") (name "unconnected-(U6-TEMP-Pad6)") (class "Default")
      (node (ref "U6") (pin "6") (pinfunction "TEMP_6") (pintype "bidirectional"))
    )
    (net (code "95") (name "unconnected-(U8-BP-PadP4)") (class "Default")
      (node (ref "U8") (pin "P4") (pinfunction "BP_P4") (pintype "bidirectional"))
    )
    (net (code "96") (name "unconnected-(U9-VT-Pad1)") (class "Default")
      (node (ref "U9") (pin "1") (pinfunction "VT_1") (pintype "bidirectional"))
    )
  )
)
